# Wiegand.net
KiCad netlist of a schematic drawn in EAGLE
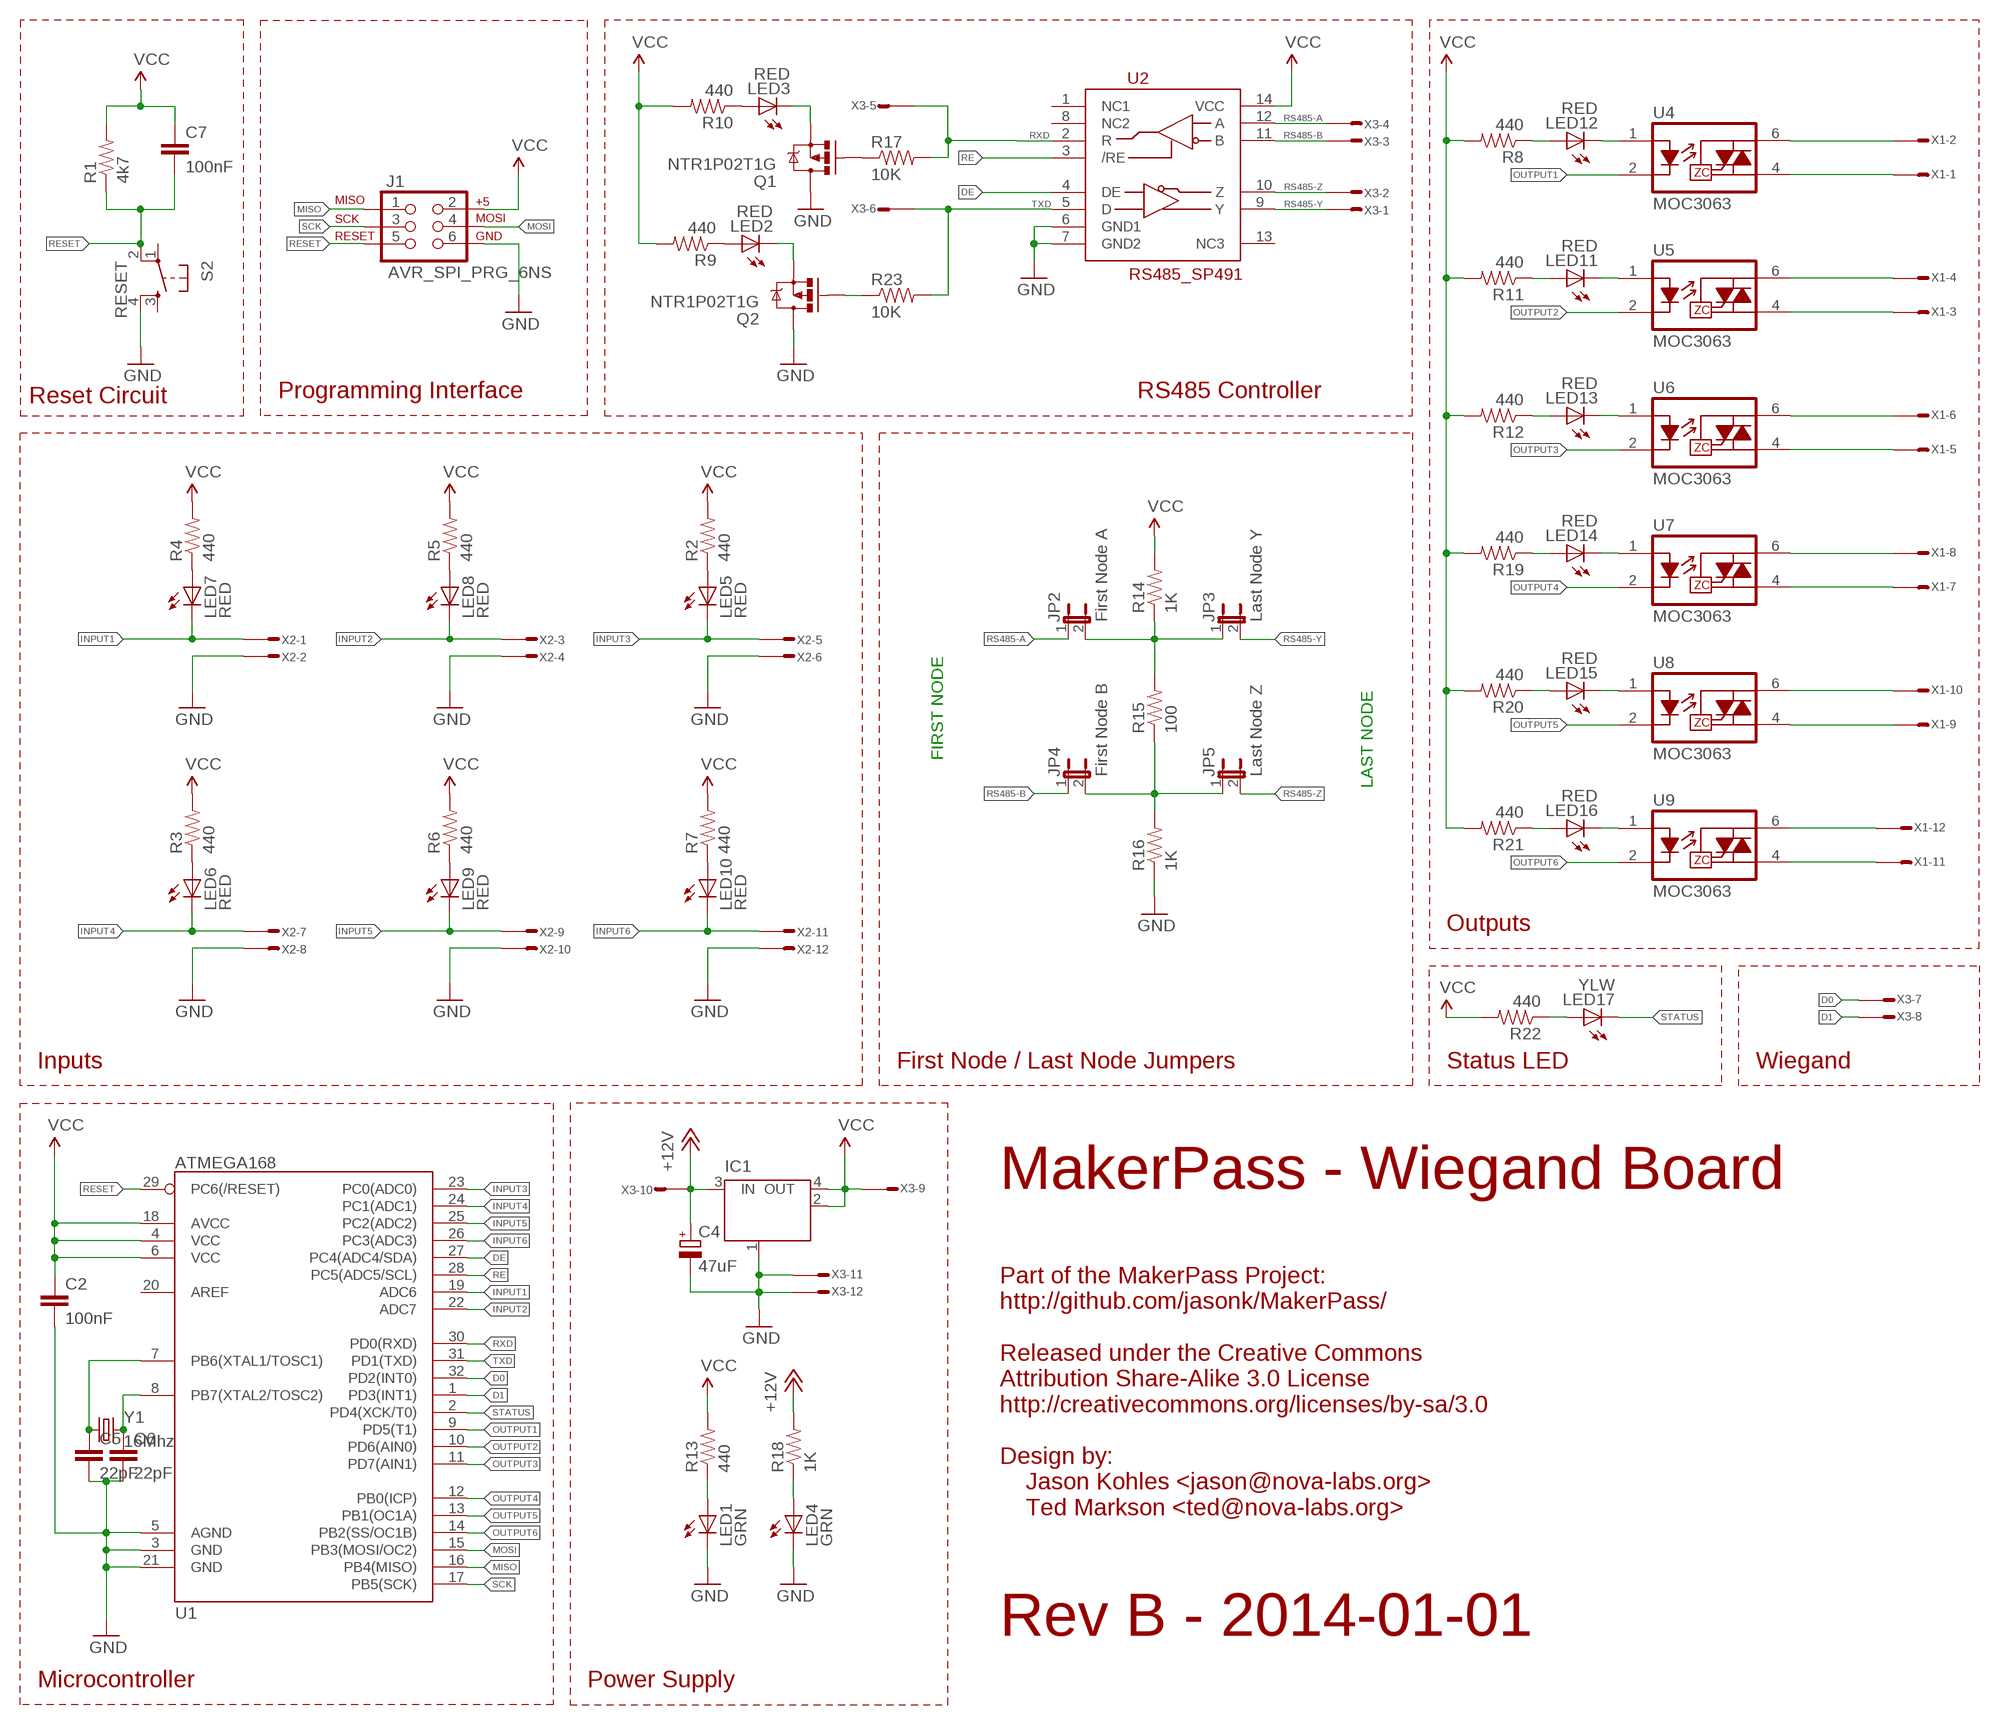
[diagram p0: schematic, sheet 1]

(export (version "E")
  (design (tool "Eeschema 10.0.6"))
  (components
    (comp (ref "C2")
      (value "100nF")
      (footprint "eagle-import:0603-CAP")
      (libsource (lib "eagle-import") (part "CAP0603-CAP"))
    )
    (comp (ref "C4")
      (value "47uF")
      (footprint "eagle-import:PANASONIC_D")
      (libsource (lib "eagle-import") (part "CPOL-EUD"))
    )
    (comp (ref "C5")
      (value "22pF")
      (footprint "eagle-import:0603-CAP")
      (libsource (lib "eagle-import") (part "CAP0603-CAP"))
    )
    (comp (ref "C6")
      (value "22pF")
      (footprint "eagle-import:0603-CAP")
      (libsource (lib "eagle-import") (part "CAP0603-CAP"))
    )
    (comp (ref "C7")
      (value "100nF")
      (footprint "eagle-import:0603-CAP")
      (libsource (lib "eagle-import") (part "CAP0603-CAP"))
    )
    (comp (ref "IC1")
      (value "MC33269ST-3.3T3")
      (footprint "eagle-import:SOT223")
      (libsource (lib "eagle-import") (part "MC33269ST-3.3T3"))
    )
    (comp (ref "J1")
      (value "AVR_SPI_PRG_6NS")
      (footprint "eagle-import:2X3-NS")
      (libsource (lib "eagle-import") (part "AVR_SPI_PRG_6NS"))
    )
    (comp (ref "JP2")
      (value "First Node A")
      (footprint "eagle-import:1X02")
      (libsource (lib "eagle-import") (part "JUMPER-2PTH"))
    )
    (comp (ref "JP3")
      (value "Last Node Y")
      (footprint "eagle-import:1X02")
      (libsource (lib "eagle-import") (part "JUMPER-2PTH"))
    )
    (comp (ref "JP4")
      (value "First Node B")
      (footprint "eagle-import:1X02")
      (libsource (lib "eagle-import") (part "JUMPER-2PTH"))
    )
    (comp (ref "JP5")
      (value "Last Node Z")
      (footprint "eagle-import:1X02")
      (libsource (lib "eagle-import") (part "JUMPER-2PTH"))
    )
    (comp (ref "LED1")
      (value "GRN")
      (footprint "eagle-import:LED-805")
      (libsource (lib "eagle-import") (part "LED-0805"))
    )
    (comp (ref "LED2")
      (value "RED")
      (footprint "eagle-import:LED-805")
      (libsource (lib "eagle-import") (part "LED-0805"))
    )
    (comp (ref "LED3")
      (value "RED")
      (footprint "eagle-import:LED-805")
      (libsource (lib "eagle-import") (part "LED-0805"))
    )
    (comp (ref "LED4")
      (value "GRN")
      (footprint "eagle-import:LED-805")
      (libsource (lib "eagle-import") (part "LED-0805"))
    )
    (comp (ref "LED5")
      (value "RED")
      (footprint "eagle-import:LED-805")
      (libsource (lib "eagle-import") (part "LED-0805"))
    )
    (comp (ref "LED6")
      (value "RED")
      (footprint "eagle-import:LED-805")
      (libsource (lib "eagle-import") (part "LED-0805"))
    )
    (comp (ref "LED7")
      (value "RED")
      (footprint "eagle-import:LED-805")
      (libsource (lib "eagle-import") (part "LED-0805"))
    )
    (comp (ref "LED8")
      (value "RED")
      (footprint "eagle-import:LED-805")
      (libsource (lib "eagle-import") (part "LED-0805"))
    )
    (comp (ref "LED9")
      (value "RED")
      (footprint "eagle-import:LED-805")
      (libsource (lib "eagle-import") (part "LED-0805"))
    )
    (comp (ref "LED10")
      (value "RED")
      (footprint "eagle-import:LED-805")
      (libsource (lib "eagle-import") (part "LED-0805"))
    )
    (comp (ref "LED11")
      (value "RED")
      (footprint "eagle-import:LED-805")
      (libsource (lib "eagle-import") (part "LED-0805"))
    )
    (comp (ref "LED12")
      (value "RED")
      (footprint "eagle-import:LED-805")
      (libsource (lib "eagle-import") (part "LED-0805"))
    )
    (comp (ref "LED13")
      (value "RED")
      (footprint "eagle-import:LED-805")
      (libsource (lib "eagle-import") (part "LED-0805"))
    )
    (comp (ref "LED14")
      (value "RED")
      (footprint "eagle-import:LED-805")
      (libsource (lib "eagle-import") (part "LED-0805"))
    )
    (comp (ref "LED15")
      (value "RED")
      (footprint "eagle-import:LED-805")
      (libsource (lib "eagle-import") (part "LED-0805"))
    )
    (comp (ref "LED16")
      (value "RED")
      (footprint "eagle-import:LED-805")
      (libsource (lib "eagle-import") (part "LED-0805"))
    )
    (comp (ref "LED17")
      (value "YLW")
      (footprint "eagle-import:LED-805")
      (libsource (lib "eagle-import") (part "LED-0805"))
    )
    (comp (ref "Q1")
      (value "NTR1P02T1G")
      (footprint "eagle-import:SOT23-3")
      (libsource (lib "eagle-import") (part "MOSFET-PCHANNELSMD"))
    )
    (comp (ref "Q2")
      (value "NTR1P02T1G")
      (footprint "eagle-import:SOT23-3")
      (libsource (lib "eagle-import") (part "MOSFET-PCHANNELSMD"))
    )
    (comp (ref "R1")
      (value "4k7")
      (footprint "eagle-import:0603-RES")
      (libsource (lib "eagle-import") (part "RESISTOR0603-RES"))
    )
    (comp (ref "R2")
      (value "440")
      (footprint "eagle-import:0603-RES")
      (libsource (lib "eagle-import") (part "RESISTOR0603-RES"))
    )
    (comp (ref "R3")
      (value "440")
      (footprint "eagle-import:0603-RES")
      (libsource (lib "eagle-import") (part "RESISTOR0603-RES"))
    )
    (comp (ref "R4")
      (value "440")
      (footprint "eagle-import:0603-RES")
      (libsource (lib "eagle-import") (part "RESISTOR0603-RES"))
    )
    (comp (ref "R5")
      (value "440")
      (footprint "eagle-import:0603-RES")
      (libsource (lib "eagle-import") (part "RESISTOR0603-RES"))
    )
    (comp (ref "R6")
      (value "440")
      (footprint "eagle-import:0603-RES")
      (libsource (lib "eagle-import") (part "RESISTOR0603-RES"))
    )
    (comp (ref "R7")
      (value "440")
      (footprint "eagle-import:0603-RES")
      (libsource (lib "eagle-import") (part "RESISTOR0603-RES"))
    )
    (comp (ref "R8")
      (value "440")
      (footprint "eagle-import:0603-RES")
      (libsource (lib "eagle-import") (part "RESISTOR0603-RES"))
    )
    (comp (ref "R9")
      (value "440")
      (footprint "eagle-import:0603-RES")
      (libsource (lib "eagle-import") (part "RESISTOR0603-RES"))
    )
    (comp (ref "R10")
      (value "440")
      (footprint "eagle-import:0603-RES")
      (libsource (lib "eagle-import") (part "RESISTOR0603-RES"))
    )
    (comp (ref "R11")
      (value "440")
      (footprint "eagle-import:0603-RES")
      (libsource (lib "eagle-import") (part "RESISTOR0603-RES"))
    )
    (comp (ref "R12")
      (value "440")
      (footprint "eagle-import:0603-RES")
      (libsource (lib "eagle-import") (part "RESISTOR0603-RES"))
    )
    (comp (ref "R13")
      (value "440")
      (footprint "eagle-import:0603-RES")
      (libsource (lib "eagle-import") (part "RESISTOR0603-RES"))
    )
    (comp (ref "R14")
      (value "1K")
      (footprint "eagle-import:0603-RES")
      (libsource (lib "eagle-import") (part "RESISTOR0603-RES"))
    )
    (comp (ref "R15")
      (value "100")
      (footprint "eagle-import:0603-RES")
      (libsource (lib "eagle-import") (part "RESISTOR0603-RES"))
    )
    (comp (ref "R16")
      (value "1K")
      (footprint "eagle-import:0603-RES")
      (libsource (lib "eagle-import") (part "RESISTOR0603-RES"))
    )
    (comp (ref "R17")
      (value "10K")
      (footprint "eagle-import:0603-RES")
      (libsource (lib "eagle-import") (part "RESISTOR0603-RES"))
    )
    (comp (ref "R18")
      (value "1K")
      (footprint "eagle-import:0603-RES")
      (libsource (lib "eagle-import") (part "RESISTOR0603-RES"))
    )
    (comp (ref "R19")
      (value "440")
      (footprint "eagle-import:0603-RES")
      (libsource (lib "eagle-import") (part "RESISTOR0603-RES"))
    )
    (comp (ref "R20")
      (value "440")
      (footprint "eagle-import:0603-RES")
      (libsource (lib "eagle-import") (part "RESISTOR0603-RES"))
    )
    (comp (ref "R21")
      (value "440")
      (footprint "eagle-import:0603-RES")
      (libsource (lib "eagle-import") (part "RESISTOR0603-RES"))
    )
    (comp (ref "R22")
      (value "440")
      (footprint "eagle-import:0603-RES")
      (libsource (lib "eagle-import") (part "RESISTOR0603-RES"))
    )
    (comp (ref "R23")
      (value "10K")
      (footprint "eagle-import:0603-RES")
      (libsource (lib "eagle-import") (part "RESISTOR0603-RES"))
    )
    (comp (ref "S2")
      (value "RESET")
      (footprint "eagle-import:TACTILE_SWITCH_SMD")
      (libsource (lib "eagle-import") (part "TAC_SWITCHSMD"))
    )
    (comp (ref "U1")
      (value "ATMEGA168")
      (footprint "eagle-import:TQFP32-08")
      (libsource (lib "eagle-import") (part "ATMEGA168"))
    )
    (comp (ref "U2")
      (value "RS485_SP491")
      (footprint "eagle-import:SOIC-14")
      (libsource (lib "eagle-import") (part "RS485_SP491"))
    )
    (comp (ref "U4")
      (value "MOC3063")
      (footprint "eagle-import:DIP8SMD")
      (libsource (lib "eagle-import") (part "MOC3063S"))
    )
    (comp (ref "U5")
      (value "MOC3063")
      (footprint "eagle-import:DIP8SMD")
      (libsource (lib "eagle-import") (part "MOC3063S"))
    )
    (comp (ref "U6")
      (value "MOC3063")
      (footprint "eagle-import:DIP8SMD")
      (libsource (lib "eagle-import") (part "MOC3063S"))
    )
    (comp (ref "U7")
      (value "MOC3063")
      (footprint "eagle-import:DIP8SMD")
      (libsource (lib "eagle-import") (part "MOC3063S"))
    )
    (comp (ref "U8")
      (value "MOC3063")
      (footprint "eagle-import:DIP8SMD")
      (libsource (lib "eagle-import") (part "MOC3063S"))
    )
    (comp (ref "U9")
      (value "MOC3063")
      (footprint "eagle-import:DIP8SMD")
      (libsource (lib "eagle-import") (part "MOC3063S"))
    )
    (comp (ref "X1")
      (value "CON-1X12-TERMBLOCK-3.5MM")
      (footprint "eagle-import:CON-1X12-TERMBLOCK-3.5MM")
      (fields (field (name "MFG_PN") "OSTTE120104"))
      (libsource (lib "eagle-import") (part "CON-1X12-TERMBLOCK-3.5MM"))
    )
    (comp (ref "X2")
      (value "CON-1X12-TERMBLOCK-3.5MM")
      (footprint "eagle-import:CON-1X12-TERMBLOCK-3.5MM")
      (fields (field (name "MFG_PN") "OSTTE120104"))
      (libsource (lib "eagle-import") (part "CON-1X12-TERMBLOCK-3.5MM"))
    )
    (comp (ref "X3")
      (value "CON-1X12-TERMBLOCK-3.5MM")
      (footprint "eagle-import:CON-1X12-TERMBLOCK-3.5MM")
      (fields (field (name "MFG_PN") "OSTTE120104"))
      (libsource (lib "eagle-import") (part "CON-1X12-TERMBLOCK-3.5MM"))
    )
    (comp (ref "Y1")
      (value "16Mhz")
      (footprint "eagle-import:HC49UP")
      (libsource (lib "eagle-import") (part "CRYSTALSMD"))
    )
  )
  (nets
    (net (code "1") (name "+12V") (class "Default")
      (node (ref "C4") (pin "+") (pinfunction "+_+") (pintype "passive"))
      (node (ref "IC1") (pin "3") (pinfunction "IN_3") (pintype "input"))
      (node (ref "R18") (pin "2") (pinfunction "2_2") (pintype "passive"))
      (node (ref "X3") (pin "10") (pinfunction "S_10") (pintype "passive"))
    )
    (net (code "2") (name "D0") (class "Default")
      (node (ref "U1") (pin "32") (pinfunction "PD2(INT0)_32") (pintype "bidirectional"))
      (node (ref "X3") (pin "7") (pinfunction "S_7") (pintype "passive"))
    )
    (net (code "3") (name "D1") (class "Default")
      (node (ref "U1") (pin "1") (pinfunction "PD3(INT1)_1") (pintype "bidirectional"))
      (node (ref "X3") (pin "8") (pinfunction "S_8") (pintype "passive"))
    )
    (net (code "4") (name "DE") (class "Default")
      (node (ref "U1") (pin "27") (pinfunction "PC4(ADC4/SDA)_27") (pintype "bidirectional"))
      (node (ref "U2") (pin "4") (pinfunction "DE_4") (pintype "bidirectional"))
    )
    (net (code "5") (name "GND") (class "Default")
      (node (ref "C2") (pin "2") (pinfunction "2_2") (pintype "passive"))
      (node (ref "C4") (pin "-") (pinfunction "-_-") (pintype "passive"))
      (node (ref "C5") (pin "2") (pinfunction "2_2") (pintype "passive"))
      (node (ref "C6") (pin "2") (pinfunction "2_2") (pintype "passive"))
      (node (ref "IC1") (pin "1") (pinfunction "GND/ADJ_1") (pintype "input"))
      (node (ref "J1") (pin "6") (pinfunction "6_6") (pintype "passive"))
      (node (ref "LED1") (pin "C") (pinfunction "C_C") (pintype "passive"))
      (node (ref "LED4") (pin "C") (pinfunction "C_C") (pintype "passive"))
      (node (ref "Q1") (pin "3") (pinfunction "D_3") (pintype "passive"))
      (node (ref "Q2") (pin "3") (pinfunction "D_3") (pintype "passive"))
      (node (ref "R16") (pin "1") (pinfunction "1_1") (pintype "passive"))
      (node (ref "S2") (pin "4") (pinfunction "4_4") (pintype "passive"))
      (node (ref "U1") (pin "21") (pinfunction "GND_21") (pintype "bidirectional"))
      (node (ref "U1") (pin "3") (pinfunction "GND_3") (pintype "bidirectional"))
      (node (ref "U1") (pin "5") (pinfunction "AGND_5") (pintype "bidirectional"))
      (node (ref "U2") (pin "6") (pinfunction "GND1_6") (pintype "bidirectional"))
      (node (ref "U2") (pin "7") (pinfunction "GND2_7") (pintype "bidirectional"))
      (node (ref "X2") (pin "10") (pinfunction "S_10") (pintype "passive"))
      (node (ref "X2") (pin "12") (pinfunction "S_12") (pintype "passive"))
      (node (ref "X2") (pin "2") (pinfunction "S_2") (pintype "passive"))
      (node (ref "X2") (pin "4") (pinfunction "S_4") (pintype "passive"))
      (node (ref "X2") (pin "6") (pinfunction "S_6") (pintype "passive"))
      (node (ref "X2") (pin "8") (pinfunction "S_8") (pintype "passive"))
      (node (ref "X3") (pin "11") (pinfunction "S_11") (pintype "passive"))
      (node (ref "X3") (pin "12") (pinfunction "S_12") (pintype "passive"))
    )
    (net (code "6") (name "INPUT1") (class "Default")
      (node (ref "LED7") (pin "C") (pinfunction "C_C") (pintype "passive"))
      (node (ref "U1") (pin "19") (pinfunction "ADC6_19") (pintype "bidirectional"))
      (node (ref "X2") (pin "1") (pinfunction "S_1") (pintype "passive"))
    )
    (net (code "7") (name "INPUT2") (class "Default")
      (node (ref "LED8") (pin "C") (pinfunction "C_C") (pintype "passive"))
      (node (ref "U1") (pin "22") (pinfunction "ADC7_22") (pintype "bidirectional"))
      (node (ref "X2") (pin "3") (pinfunction "S_3") (pintype "passive"))
    )
    (net (code "8") (name "INPUT3") (class "Default")
      (node (ref "LED5") (pin "C") (pinfunction "C_C") (pintype "passive"))
      (node (ref "U1") (pin "23") (pinfunction "PC0(ADC0)_23") (pintype "bidirectional"))
      (node (ref "X2") (pin "5") (pinfunction "S_5") (pintype "passive"))
    )
    (net (code "9") (name "INPUT4") (class "Default")
      (node (ref "LED6") (pin "C") (pinfunction "C_C") (pintype "passive"))
      (node (ref "U1") (pin "24") (pinfunction "PC1(ADC1)_24") (pintype "bidirectional"))
      (node (ref "X2") (pin "7") (pinfunction "S_7") (pintype "passive"))
    )
    (net (code "10") (name "INPUT5") (class "Default")
      (node (ref "LED9") (pin "C") (pinfunction "C_C") (pintype "passive"))
      (node (ref "U1") (pin "25") (pinfunction "PC2(ADC2)_25") (pintype "bidirectional"))
      (node (ref "X2") (pin "9") (pinfunction "S_9") (pintype "passive"))
    )
    (net (code "11") (name "INPUT6") (class "Default")
      (node (ref "LED10") (pin "C") (pinfunction "C_C") (pintype "passive"))
      (node (ref "U1") (pin "26") (pinfunction "PC3(ADC3)_26") (pintype "bidirectional"))
      (node (ref "X2") (pin "11") (pinfunction "S_11") (pintype "passive"))
    )
    (net (code "12") (name "MISO") (class "Default")
      (node (ref "J1") (pin "1") (pinfunction "1_1") (pintype "passive"))
      (node (ref "U1") (pin "16") (pinfunction "PB4(MISO)_16") (pintype "bidirectional"))
    )
    (net (code "13") (name "MOSI") (class "Default")
      (node (ref "J1") (pin "4") (pinfunction "4_4") (pintype "passive"))
      (node (ref "U1") (pin "15") (pinfunction "PB3(MOSI/OC2)_15") (pintype "bidirectional"))
    )
    (net (code "14") (name "Net-(JP2-Pad2)") (class "Default")
      (node (ref "JP2") (pin "2") (pinfunction "2_2") (pintype "passive"))
      (node (ref "JP3") (pin "1") (pinfunction "1_1") (pintype "passive"))
      (node (ref "R14") (pin "1") (pinfunction "1_1") (pintype "passive"))
      (node (ref "R15") (pin "2") (pinfunction "2_2") (pintype "passive"))
    )
    (net (code "15") (name "Net-(JP4-Pad2)") (class "Default")
      (node (ref "JP4") (pin "2") (pinfunction "2_2") (pintype "passive"))
      (node (ref "JP5") (pin "1") (pinfunction "1_1") (pintype "passive"))
      (node (ref "R15") (pin "1") (pinfunction "1_1") (pintype "passive"))
      (node (ref "R16") (pin "2") (pinfunction "2_2") (pintype "passive"))
    )
    (net (code "16") (name "Net-(LED1-PadA)") (class "Default")
      (node (ref "LED1") (pin "A") (pinfunction "A_A") (pintype "passive"))
      (node (ref "R13") (pin "1") (pinfunction "1_1") (pintype "passive"))
    )
    (net (code "17") (name "Net-(LED2-PadA)") (class "Default")
      (node (ref "LED2") (pin "A") (pinfunction "A_A") (pintype "passive"))
      (node (ref "R9") (pin "1") (pinfunction "1_1") (pintype "passive"))
    )
    (net (code "18") (name "Net-(LED3-PadA)") (class "Default")
      (node (ref "LED3") (pin "A") (pinfunction "A_A") (pintype "passive"))
      (node (ref "R10") (pin "1") (pinfunction "1_1") (pintype "passive"))
    )
    (net (code "19") (name "Net-(LED4-PadA)") (class "Default")
      (node (ref "LED4") (pin "A") (pinfunction "A_A") (pintype "passive"))
      (node (ref "R18") (pin "1") (pinfunction "1_1") (pintype "passive"))
    )
    (net (code "20") (name "Net-(LED5-PadA)") (class "Default")
      (node (ref "LED5") (pin "A") (pinfunction "A_A") (pintype "passive"))
      (node (ref "R2") (pin "1") (pinfunction "1_1") (pintype "passive"))
    )
    (net (code "21") (name "Net-(LED6-PadA)") (class "Default")
      (node (ref "LED6") (pin "A") (pinfunction "A_A") (pintype "passive"))
      (node (ref "R3") (pin "1") (pinfunction "1_1") (pintype "passive"))
    )
    (net (code "22") (name "Net-(LED7-PadA)") (class "Default")
      (node (ref "LED7") (pin "A") (pinfunction "A_A") (pintype "passive"))
      (node (ref "R4") (pin "1") (pinfunction "1_1") (pintype "passive"))
    )
    (net (code "23") (name "Net-(LED8-PadA)") (class "Default")
      (node (ref "LED8") (pin "A") (pinfunction "A_A") (pintype "passive"))
      (node (ref "R5") (pin "1") (pinfunction "1_1") (pintype "passive"))
    )
    (net (code "24") (name "Net-(LED9-PadA)") (class "Default")
      (node (ref "LED9") (pin "A") (pinfunction "A_A") (pintype "passive"))
      (node (ref "R6") (pin "1") (pinfunction "1_1") (pintype "passive"))
    )
    (net (code "25") (name "Net-(LED10-PadA)") (class "Default")
      (node (ref "LED10") (pin "A") (pinfunction "A_A") (pintype "passive"))
      (node (ref "R7") (pin "1") (pinfunction "1_1") (pintype "passive"))
    )
    (net (code "26") (name "Net-(LED11-PadA)") (class "Default")
      (node (ref "LED11") (pin "A") (pinfunction "A_A") (pintype "passive"))
      (node (ref "R11") (pin "1") (pinfunction "1_1") (pintype "passive"))
    )
    (net (code "27") (name "Net-(LED12-PadA)") (class "Default")
      (node (ref "LED12") (pin "A") (pinfunction "A_A") (pintype "passive"))
      (node (ref "R8") (pin "1") (pinfunction "1_1") (pintype "passive"))
    )
    (net (code "28") (name "Net-(LED13-PadA)") (class "Default")
      (node (ref "LED13") (pin "A") (pinfunction "A_A") (pintype "passive"))
      (node (ref "R12") (pin "1") (pinfunction "1_1") (pintype "passive"))
    )
    (net (code "29") (name "Net-(LED14-PadA)") (class "Default")
      (node (ref "LED14") (pin "A") (pinfunction "A_A") (pintype "passive"))
      (node (ref "R19") (pin "1") (pinfunction "1_1") (pintype "passive"))
    )
    (net (code "30") (name "Net-(LED15-PadA)") (class "Default")
      (node (ref "LED15") (pin "A") (pinfunction "A_A") (pintype "passive"))
      (node (ref "R20") (pin "1") (pinfunction "1_1") (pintype "passive"))
    )
    (net (code "31") (name "Net-(LED16-PadA)") (class "Default")
      (node (ref "LED16") (pin "A") (pinfunction "A_A") (pintype "passive"))
      (node (ref "R21") (pin "1") (pinfunction "1_1") (pintype "passive"))
    )
    (net (code "32") (name "Net-(LED17-PadA)") (class "Default")
      (node (ref "LED17") (pin "A") (pinfunction "A_A") (pintype "passive"))
      (node (ref "R22") (pin "1") (pinfunction "1_1") (pintype "passive"))
    )
    (net (code "33") (name "Net-(Q1-G)") (class "Default")
      (node (ref "Q1") (pin "1") (pinfunction "G_1") (pintype "passive"))
      (node (ref "R17") (pin "1") (pinfunction "1_1") (pintype "passive"))
    )
    (net (code "34") (name "Net-(Q1-S)") (class "Default")
      (node (ref "LED3") (pin "C") (pinfunction "C_C") (pintype "passive"))
      (node (ref "Q1") (pin "2") (pinfunction "S_2") (pintype "passive"))
    )
    (net (code "35") (name "Net-(Q2-G)") (class "Default")
      (node (ref "Q2") (pin "1") (pinfunction "G_1") (pintype "passive"))
      (node (ref "R23") (pin "1") (pinfunction "1_1") (pintype "passive"))
    )
    (net (code "36") (name "Net-(Q2-S)") (class "Default")
      (node (ref "LED2") (pin "C") (pinfunction "C_C") (pintype "passive"))
      (node (ref "Q2") (pin "2") (pinfunction "S_2") (pintype "passive"))
    )
    (net (code "37") (name "Net-(U1-PB6(XTAL1{slash}TOSC1))") (class "Default")
      (node (ref "C5") (pin "1") (pinfunction "1_1") (pintype "passive"))
      (node (ref "U1") (pin "7") (pinfunction "PB6(XTAL1/TOSC1)_7") (pintype "bidirectional"))
      (node (ref "Y1") (pin "1") (pinfunction "1_1") (pintype "passive"))
    )
    (net (code "38") (name "Net-(U1-PB7(XTAL2{slash}TOSC2))") (class "Default")
      (node (ref "C6") (pin "1") (pinfunction "1_1") (pintype "passive"))
      (node (ref "U1") (pin "8") (pinfunction "PB7(XTAL2/TOSC2)_8") (pintype "bidirectional"))
      (node (ref "Y1") (pin "2") (pinfunction "2_2") (pintype "passive"))
    )
    (net (code "39") (name "Net-(U4-A)") (class "Default")
      (node (ref "LED12") (pin "C") (pinfunction "C_C") (pintype "passive"))
      (node (ref "U4") (pin "1") (pinfunction "A_1") (pintype "bidirectional"))
    )
    (net (code "40") (name "Net-(U4-T1)") (class "Default")
      (node (ref "U4") (pin "6") (pinfunction "T1_6") (pintype "bidirectional"))
      (node (ref "X1") (pin "2") (pinfunction "S_2") (pintype "passive"))
    )
    (net (code "41") (name "Net-(U4-T2)") (class "Default")
      (node (ref "U4") (pin "4") (pinfunction "T2_4") (pintype "bidirectional"))
      (node (ref "X1") (pin "1") (pinfunction "S_1") (pintype "passive"))
    )
    (net (code "42") (name "Net-(U5-A)") (class "Default")
      (node (ref "LED11") (pin "C") (pinfunction "C_C") (pintype "passive"))
      (node (ref "U5") (pin "1") (pinfunction "A_1") (pintype "bidirectional"))
    )
    (net (code "43") (name "Net-(U5-T1)") (class "Default")
      (node (ref "U5") (pin "6") (pinfunction "T1_6") (pintype "bidirectional"))
      (node (ref "X1") (pin "4") (pinfunction "S_4") (pintype "passive"))
    )
    (net (code "44") (name "Net-(U5-T2)") (class "Default")
      (node (ref "U5") (pin "4") (pinfunction "T2_4") (pintype "bidirectional"))
      (node (ref "X1") (pin "3") (pinfunction "S_3") (pintype "passive"))
    )
    (net (code "45") (name "Net-(U6-A)") (class "Default")
      (node (ref "LED13") (pin "C") (pinfunction "C_C") (pintype "passive"))
      (node (ref "U6") (pin "1") (pinfunction "A_1") (pintype "bidirectional"))
    )
    (net (code "46") (name "Net-(U6-T1)") (class "Default")
      (node (ref "U6") (pin "6") (pinfunction "T1_6") (pintype "bidirectional"))
      (node (ref "X1") (pin "6") (pinfunction "S_6") (pintype "passive"))
    )
    (net (code "47") (name "Net-(U6-T2)") (class "Default")
      (node (ref "U6") (pin "4") (pinfunction "T2_4") (pintype "bidirectional"))
      (node (ref "X1") (pin "5") (pinfunction "S_5") (pintype "passive"))
    )
    (net (code "48") (name "Net-(U7-A)") (class "Default")
      (node (ref "LED14") (pin "C") (pinfunction "C_C") (pintype "passive"))
      (node (ref "U7") (pin "1") (pinfunction "A_1") (pintype "bidirectional"))
    )
    (net (code "49") (name "Net-(U7-T1)") (class "Default")
      (node (ref "U7") (pin "6") (pinfunction "T1_6") (pintype "bidirectional"))
      (node (ref "X1") (pin "8") (pinfunction "S_8") (pintype "passive"))
    )
    (net (code "50") (name "Net-(U7-T2)") (class "Default")
      (node (ref "U7") (pin "4") (pinfunction "T2_4") (pintype "bidirectional"))
      (node (ref "X1") (pin "7") (pinfunction "S_7") (pintype "passive"))
    )
    (net (code "51") (name "Net-(U8-A)") (class "Default")
      (node (ref "LED15") (pin "C") (pinfunction "C_C") (pintype "passive"))
      (node (ref "U8") (pin "1") (pinfunction "A_1") (pintype "bidirectional"))
    )
    (net (code "52") (name "Net-(U8-T1)") (class "Default")
      (node (ref "U8") (pin "6") (pinfunction "T1_6") (pintype "bidirectional"))
      (node (ref "X1") (pin "10") (pinfunction "S_10") (pintype "passive"))
    )
    (net (code "53") (name "Net-(U8-T2)") (class "Default")
      (node (ref "U8") (pin "4") (pinfunction "T2_4") (pintype "bidirectional"))
      (node (ref "X1") (pin "9") (pinfunction "S_9") (pintype "passive"))
    )
    (net (code "54") (name "Net-(U9-A)") (class "Default")
      (node (ref "LED16") (pin "C") (pinfunction "C_C") (pintype "passive"))
      (node (ref "U9") (pin "1") (pinfunction "A_1") (pintype "bidirectional"))
    )
    (net (code "55") (name "Net-(U9-T1)") (class "Default")
      (node (ref "U9") (pin "6") (pinfunction "T1_6") (pintype "bidirectional"))
      (node (ref "X1") (pin "12") (pinfunction "S_12") (pintype "passive"))
    )
    (net (code "56") (name "Net-(U9-T2)") (class "Default")
      (node (ref "U9") (pin "4") (pinfunction "T2_4") (pintype "bidirectional"))
      (node (ref "X1") (pin "11") (pinfunction "S_11") (pintype "passive"))
    )
    (net (code "57") (name "OUTPUT1") (class "Default")
      (node (ref "U1") (pin "9") (pinfunction "PD5(T1)_9") (pintype "bidirectional"))
      (node (ref "U4") (pin "2") (pinfunction "K_2") (pintype "bidirectional"))
    )
    (net (code "58") (name "OUTPUT2") (class "Default")
      (node (ref "U1") (pin "10") (pinfunction "PD6(AIN0)_10") (pintype "bidirectional"))
      (node (ref "U5") (pin "2") (pinfunction "K_2") (pintype "bidirectional"))
    )
    (net (code "59") (name "OUTPUT3") (class "Default")
      (node (ref "U1") (pin "11") (pinfunction "PD7(AIN1)_11") (pintype "bidirectional"))
      (node (ref "U6") (pin "2") (pinfunction "K_2") (pintype "bidirectional"))
    )
    (net (code "60") (name "OUTPUT4") (class "Default")
      (node (ref "U1") (pin "12") (pinfunction "PB0(ICP)_12") (pintype "bidirectional"))
      (node (ref "U7") (pin "2") (pinfunction "K_2") (pintype "bidirectional"))
    )
    (net (code "61") (name "OUTPUT5") (class "Default")
      (node (ref "U1") (pin "13") (pinfunction "PB1(OC1A)_13") (pintype "bidirectional"))
      (node (ref "U8") (pin "2") (pinfunction "K_2") (pintype "bidirectional"))
    )
    (net (code "62") (name "OUTPUT6") (class "Default")
      (node (ref "U1") (pin "14") (pinfunction "PB2(SS/OC1B)_14") (pintype "bidirectional"))
      (node (ref "U9") (pin "2") (pinfunction "K_2") (pintype "bidirectional"))
    )
    (net (code "63") (name "RE") (class "Default")
      (node (ref "U1") (pin "28") (pinfunction "PC5(ADC5/SCL)_28") (pintype "bidirectional"))
      (node (ref "U2") (pin "3") (pinfunction "/RE_3") (pintype "bidirectional"))
    )
    (net (code "64") (name "RESET") (class "Default")
      (node (ref "C7") (pin "2") (pinfunction "2_2") (pintype "passive"))
      (node (ref "J1") (pin "5") (pinfunction "5_5") (pintype "passive"))
      (node (ref "R1") (pin "1") (pinfunction "1_1") (pintype "passive"))
      (node (ref "S2") (pin "2") (pinfunction "2_2") (pintype "passive"))
      (node (ref "U1") (pin "29") (pinfunction "PC6(/RESET)_29") (pintype "bidirectional"))
    )
    (net (code "65") (name "RS485-A") (class "Default")
      (node (ref "JP2") (pin "1") (pinfunction "1_1") (pintype "passive"))
      (node (ref "U2") (pin "12") (pinfunction "A_12") (pintype "bidirectional"))
      (node (ref "X3") (pin "4") (pinfunction "S_4") (pintype "passive"))
    )
    (net (code "66") (name "RS485-B") (class "Default")
      (node (ref "JP4") (pin "1") (pinfunction "1_1") (pintype "passive"))
      (node (ref "U2") (pin "11") (pinfunction "B_11") (pintype "bidirectional"))
      (node (ref "X3") (pin "3") (pinfunction "S_3") (pintype "passive"))
    )
    (net (code "67") (name "RS485-Y") (class "Default")
      (node (ref "JP3") (pin "2") (pinfunction "2_2") (pintype "passive"))
      (node (ref "U2") (pin "9") (pinfunction "Y_9") (pintype "bidirectional"))
      (node (ref "X3") (pin "1") (pinfunction "S_1") (pintype "passive"))
    )
    (net (code "68") (name "RS485-Z") (class "Default")
      (node (ref "JP5") (pin "2") (pinfunction "2_2") (pintype "passive"))
      (node (ref "U2") (pin "10") (pinfunction "Z_10") (pintype "bidirectional"))
      (node (ref "X3") (pin "2") (pinfunction "S_2") (pintype "passive"))
    )
    (net (code "69") (name "RXD") (class "Default")
      (node (ref "R17") (pin "2") (pinfunction "2_2") (pintype "passive"))
      (node (ref "U1") (pin "30") (pinfunction "PD0(RXD)_30") (pintype "bidirectional"))
      (node (ref "U2") (pin "2") (pinfunction "R_2") (pintype "bidirectional"))
      (node (ref "X3") (pin "5") (pinfunction "S_5") (pintype "passive"))
    )
    (net (code "70") (name "SCK") (class "Default")
      (node (ref "J1") (pin "3") (pinfunction "3_3") (pintype "passive"))
      (node (ref "U1") (pin "17") (pinfunction "PB5(SCK)_17") (pintype "bidirectional"))
    )
    (net (code "71") (name "STATUS") (class "Default")
      (node (ref "LED17") (pin "C") (pinfunction "C_C") (pintype "passive"))
      (node (ref "U1") (pin "2") (pinfunction "PD4(XCK/T0)_2") (pintype "bidirectional"))
    )
    (net (code "72") (name "TXD") (class "Default")
      (node (ref "R23") (pin "2") (pinfunction "2_2") (pintype "passive"))
      (node (ref "U1") (pin "31") (pinfunction "PD1(TXD)_31") (pintype "bidirectional"))
      (node (ref "U2") (pin "5") (pinfunction "D_5") (pintype "bidirectional"))
      (node (ref "X3") (pin "6") (pinfunction "S_6") (pintype "passive"))
    )
    (net (code "73") (name "VCC") (class "Default")
      (node (ref "C2") (pin "1") (pinfunction "1_1") (pintype "passive"))
      (node (ref "C7") (pin "1") (pinfunction "1_1") (pintype "passive"))
      (node (ref "IC1") (pin "2") (pinfunction "OUT_2") (pintype "passive"))
      (node (ref "IC1") (pin "4") (pinfunction "OUT_4") (pintype "passive"))
      (node (ref "J1") (pin "2") (pinfunction "2_2") (pintype "passive"))
      (node (ref "R1") (pin "2") (pinfunction "2_2") (pintype "passive"))
      (node (ref "R10") (pin "2") (pinfunction "2_2") (pintype "passive"))
      (node (ref "R11") (pin "2") (pinfunction "2_2") (pintype "passive"))
      (node (ref "R12") (pin "2") (pinfunction "2_2") (pintype "passive"))
      (node (ref "R13") (pin "2") (pinfunction "2_2") (pintype "passive"))
      (node (ref "R14") (pin "2") (pinfunction "2_2") (pintype "passive"))
      (node (ref "R19") (pin "2") (pinfunction "2_2") (pintype "passive"))
      (node (ref "R2") (pin "2") (pinfunction "2_2") (pintype "passive"))
      (node (ref "R20") (pin "2") (pinfunction "2_2") (pintype "passive"))
      (node (ref "R21") (pin "2") (pinfunction "2_2") (pintype "passive"))
      (node (ref "R22") (pin "2") (pinfunction "2_2") (pintype "passive"))
      (node (ref "R3") (pin "2") (pinfunction "2_2") (pintype "passive"))
      (node (ref "R4") (pin "2") (pinfunction "2_2") (pintype "passive"))
      (node (ref "R5") (pin "2") (pinfunction "2_2") (pintype "passive"))
      (node (ref "R6") (pin "2") (pinfunction "2_2") (pintype "passive"))
      (node (ref "R7") (pin "2") (pinfunction "2_2") (pintype "passive"))
      (node (ref "R8") (pin "2") (pinfunction "2_2") (pintype "passive"))
      (node (ref "R9") (pin "2") (pinfunction "2_2") (pintype "passive"))
      (node (ref "U1") (pin "18") (pinfunction "AVCC_18") (pintype "bidirectional"))
      (node (ref "U1") (pin "4") (pinfunction "VCC_4") (pintype "bidirectional"))
      (node (ref "U1") (pin "6") (pinfunction "VCC_6") (pintype "bidirectional"))
      (node (ref "U2") (pin "14") (pinfunction "VCC_14") (pintype "bidirectional"))
      (node (ref "X3") (pin "9") (pinfunction "S_9") (pintype "passive"))
    )
    (net (code "74") (name "unconnected-(S2-Pad1)") (class "Default")
      (node (ref "S2") (pin "1") (pinfunction "1_1") (pintype "passive"))
    )
    (net (code "75") (name "unconnected-(S2-Pad3)") (class "Default")
      (node (ref "S2") (pin "3") (pinfunction "3_3") (pintype "passive"))
    )
    (net (code "76") (name "unconnected-(U1-AREF-Pad20)") (class "Default")
      (node (ref "U1") (pin "20") (pinfunction "AREF_20") (pintype "bidirectional"))
    )
    (net (code "77") (name "unconnected-(U2-NC1-Pad1)") (class "Default")
      (node (ref "U2") (pin "1") (pinfunction "NC1_1") (pintype "bidirectional"))
    )
    (net (code "78") (name "unconnected-(U2-NC2-Pad8)") (class "Default")
      (node (ref "U2") (pin "8") (pinfunction "NC2_8") (pintype "bidirectional"))
    )
    (net (code "79") (name "unconnected-(U2-NC3-Pad13)") (class "Default")
      (node (ref "U2") (pin "13") (pinfunction "NC3_13") (pintype "bidirectional"))
    )
  )
)
